# robothat.net
KiCad netlist of a schematic drawn in EAGLE
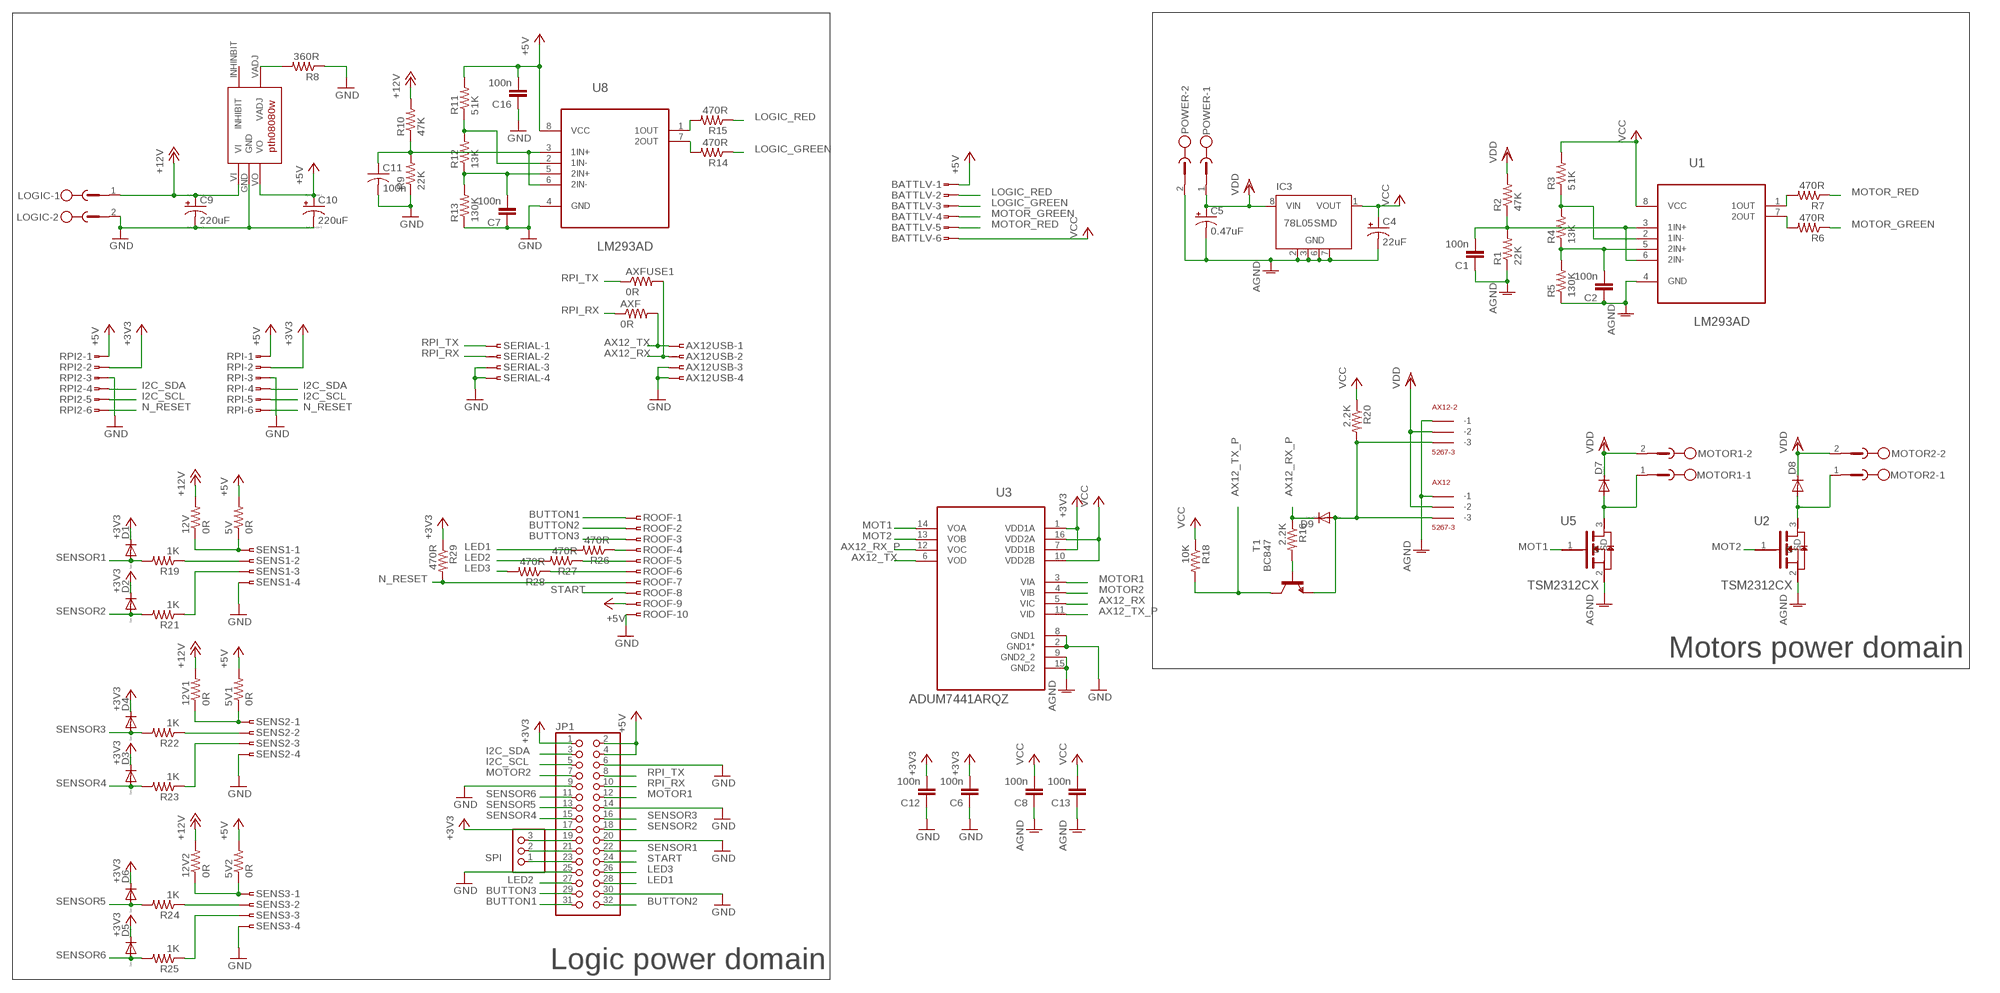
[diagram p0: schematic, sheet 1]

(export (version "E")
  (design (tool "Eeschema 10.0.6"))
  (components
    (comp (ref "5V")
      (value "0R")
      (footprint "eagle-import:R0805")
      (libsource (lib "eagle-import") (part "R-US_R0805"))
    )
    (comp (ref "5V1")
      (value "0R")
      (footprint "eagle-import:R0805")
      (libsource (lib "eagle-import") (part "R-US_R0805"))
    )
    (comp (ref "5V2")
      (value "0R")
      (footprint "eagle-import:R0805")
      (libsource (lib "eagle-import") (part "R-US_R0805"))
    )
    (comp (ref "12V")
      (value "0R")
      (footprint "eagle-import:R0805")
      (libsource (lib "eagle-import") (part "R-US_R0805"))
    )
    (comp (ref "12V1")
      (value "0R")
      (footprint "eagle-import:R0805")
      (libsource (lib "eagle-import") (part "R-US_R0805"))
    )
    (comp (ref "12V2")
      (value "0R")
      (footprint "eagle-import:R0805")
      (libsource (lib "eagle-import") (part "R-US_R0805"))
    )
    (comp (ref "AX12")
      (value "5267-3")
      (footprint "eagle-import:5267-3")
      (libsource (lib "eagle-import") (part "5267-3"))
    )
    (comp (ref "AX12-2")
      (value "5267-3")
      (footprint "eagle-import:5267-3")
      (libsource (lib "eagle-import") (part "5267-3"))
    )
    (comp (ref "AX12USB")
      (value "SMDTOP-4")
      (footprint "eagle-import:SMDTOP4")
      (libsource (lib "eagle-import") (part "SMDTOP-4"))
    )
    (comp (ref "AXF")
      (value "0R")
      (footprint "eagle-import:R0805")
      (libsource (lib "eagle-import") (part "R-US_R0805"))
    )
    (comp (ref "AXFUSE1")
      (value "0R")
      (footprint "eagle-import:R0805")
      (libsource (lib "eagle-import") (part "R-US_R0805"))
    )
    (comp (ref "BATTLV")
      (value "SMDTOP-6")
      (footprint "eagle-import:SMDTOP6")
      (libsource (lib "eagle-import") (part "SMDTOP-6"))
    )
    (comp (ref "C1")
      (value "100n")
      (footprint "eagle-import:C0805")
      (libsource (lib "eagle-import") (part "C-EUC0805"))
    )
    (comp (ref "C2")
      (value "100n")
      (footprint "eagle-import:C0805")
      (libsource (lib "eagle-import") (part "C-EUC0805"))
    )
    (comp (ref "C4")
      (value "22uF")
      (footprint "eagle-import:E2-5")
      (libsource (lib "eagle-import") (part "CPOL-USE2-5"))
    )
    (comp (ref "C5")
      (value "0.47uF")
      (footprint "eagle-import:E2-5")
      (libsource (lib "eagle-import") (part "CPOL-USE2-5"))
    )
    (comp (ref "C6")
      (value "100n")
      (footprint "eagle-import:C0805")
      (libsource (lib "eagle-import") (part "C-EUC0805"))
    )
    (comp (ref "C7")
      (value "100n")
      (footprint "eagle-import:C0805")
      (libsource (lib "eagle-import") (part "C-EUC0805"))
    )
    (comp (ref "C8")
      (value "100n")
      (footprint "eagle-import:C0805")
      (libsource (lib "eagle-import") (part "C-EUC0805"))
    )
    (comp (ref "C9")
      (value "220uF")
      (footprint "eagle-import:E3,5-8")
      (libsource (lib "eagle-import") (part "resistor_CPOL-USE3.5-8"))
    )
    (comp (ref "C10")
      (value "220uF")
      (footprint "eagle-import:E2,5-7")
      (libsource (lib "eagle-import") (part "resistor_CPOL-USE2.5-7"))
    )
    (comp (ref "C11")
      (value "100n")
      (footprint "eagle-import:C0805")
      (libsource (lib "eagle-import") (part "C-USC0805"))
    )
    (comp (ref "C12")
      (value "100n")
      (footprint "eagle-import:C0805")
      (libsource (lib "eagle-import") (part "C-EUC0805"))
    )
    (comp (ref "C13")
      (value "100n")
      (footprint "eagle-import:C0805")
      (libsource (lib "eagle-import") (part "C-EUC0805"))
    )
    (comp (ref "C16")
      (value "100n")
      (footprint "eagle-import:C0805")
      (libsource (lib "eagle-import") (part "C-EUC0805"))
    )
    (comp (ref "D1")
      (value "DIODE-SOD523")
      (footprint "eagle-import:SOD523")
      (libsource (lib "eagle-import") (part "DIODE-SOD523"))
    )
    (comp (ref "D2")
      (value "DIODE-SOD523")
      (footprint "eagle-import:SOD523")
      (libsource (lib "eagle-import") (part "DIODE-SOD523"))
    )
    (comp (ref "D3")
      (value "DIODE-SOD523")
      (footprint "eagle-import:SOD523")
      (libsource (lib "eagle-import") (part "DIODE-SOD523"))
    )
    (comp (ref "D4")
      (value "DIODE-SOD523")
      (footprint "eagle-import:SOD523")
      (libsource (lib "eagle-import") (part "DIODE-SOD523"))
    )
    (comp (ref "D5")
      (value "DIODE-SOD523")
      (footprint "eagle-import:SOD523")
      (libsource (lib "eagle-import") (part "DIODE-SOD523"))
    )
    (comp (ref "D6")
      (value "DIODE-SOD523")
      (footprint "eagle-import:SOD523")
      (libsource (lib "eagle-import") (part "DIODE-SOD523"))
    )
    (comp (ref "D7")
      (value "DIODE-SOD323-R")
      (footprint "eagle-import:SOD323-R")
      (libsource (lib "eagle-import") (part "DIODE-SOD323-R"))
    )
    (comp (ref "D8")
      (value "DIODE-SOD323-R")
      (footprint "eagle-import:SOD323-R")
      (libsource (lib "eagle-import") (part "DIODE-SOD323-R"))
    )
    (comp (ref "D9")
      (value "DIODE-SOD523")
      (footprint "eagle-import:SOD523")
      (libsource (lib "eagle-import") (part "DIODE-SOD523"))
    )
    (comp (ref "IC3")
      (value "78L05SMD")
      (footprint "eagle-import:SO08")
      (libsource (lib "eagle-import") (part "78LSMD05"))
    )
    (comp (ref "JP1")
      (value "PINHD-2X16")
      (footprint "eagle-import:2X16")
      (libsource (lib "eagle-import") (part "PINHD-2X16"))
    )
    (comp (ref "LOGIC")
      (value "MSTBV2")
      (footprint "eagle-import:MSTBV2")
      (libsource (lib "eagle-import") (part "MSTBV2"))
    )
    (comp (ref "MOTOR1")
      (value "MSTBV2")
      (footprint "eagle-import:MSTBV2")
      (libsource (lib "eagle-import") (part "MSTBV2"))
    )
    (comp (ref "MOTOR2")
      (value "MSTBV2")
      (footprint "eagle-import:MSTBV2")
      (libsource (lib "eagle-import") (part "MSTBV2"))
    )
    (comp (ref "POWER")
      (value "MSTBV2")
      (footprint "eagle-import:MSTBV2")
      (libsource (lib "eagle-import") (part "MSTBV2"))
    )
    (comp (ref "R1")
      (value "22K")
      (footprint "eagle-import:R0805")
      (libsource (lib "eagle-import") (part "R-US_R0805"))
    )
    (comp (ref "R2")
      (value "47K")
      (footprint "eagle-import:R0805")
      (libsource (lib "eagle-import") (part "R-US_R0805"))
    )
    (comp (ref "R3")
      (value "51K")
      (footprint "eagle-import:R0805")
      (libsource (lib "eagle-import") (part "R-US_R0805"))
    )
    (comp (ref "R4")
      (value "13K")
      (footprint "eagle-import:R0805")
      (libsource (lib "eagle-import") (part "R-US_R0805"))
    )
    (comp (ref "R5")
      (value "130K")
      (footprint "eagle-import:R0805")
      (libsource (lib "eagle-import") (part "R-US_R0805"))
    )
    (comp (ref "R6")
      (value "470R")
      (footprint "eagle-import:R0805")
      (libsource (lib "eagle-import") (part "R-US_R0805"))
    )
    (comp (ref "R7")
      (value "470R")
      (footprint "eagle-import:R0805")
      (libsource (lib "eagle-import") (part "R-US_R0805"))
    )
    (comp (ref "R8")
      (value "360R")
      (footprint "eagle-import:R0805")
      (libsource (lib "eagle-import") (part "R-US_R0805"))
    )
    (comp (ref "R9")
      (value "22K")
      (footprint "eagle-import:R0805")
      (libsource (lib "eagle-import") (part "R-US_R0805"))
    )
    (comp (ref "R10")
      (value "47K")
      (footprint "eagle-import:R0805")
      (libsource (lib "eagle-import") (part "R-US_R0805"))
    )
    (comp (ref "R11")
      (value "51K")
      (footprint "eagle-import:R0805")
      (libsource (lib "eagle-import") (part "R-US_R0805"))
    )
    (comp (ref "R12")
      (value "13K")
      (footprint "eagle-import:R0805")
      (libsource (lib "eagle-import") (part "R-US_R0805"))
    )
    (comp (ref "R13")
      (value "130K")
      (footprint "eagle-import:R0805")
      (libsource (lib "eagle-import") (part "R-US_R0805"))
    )
    (comp (ref "R14")
      (value "470R")
      (footprint "eagle-import:R0805")
      (libsource (lib "eagle-import") (part "R-US_R0805"))
    )
    (comp (ref "R15")
      (value "470R")
      (footprint "eagle-import:R0805")
      (libsource (lib "eagle-import") (part "R-US_R0805"))
    )
    (comp (ref "R16")
      (value "2.2K")
      (footprint "eagle-import:R0805")
      (libsource (lib "eagle-import") (part "R-US_R0805"))
    )
    (comp (ref "R18")
      (value "10K")
      (footprint "eagle-import:R0805")
      (libsource (lib "eagle-import") (part "R-US_R0805"))
    )
    (comp (ref "R19")
      (value "1K")
      (footprint "eagle-import:R0805")
      (libsource (lib "eagle-import") (part "R-US_R0805"))
    )
    (comp (ref "R20")
      (value "2.2K")
      (footprint "eagle-import:R0805")
      (libsource (lib "eagle-import") (part "R-US_R0805"))
    )
    (comp (ref "R21")
      (value "1K")
      (footprint "eagle-import:R0805")
      (libsource (lib "eagle-import") (part "R-US_R0805"))
    )
    (comp (ref "R22")
      (value "1K")
      (footprint "eagle-import:R0805")
      (libsource (lib "eagle-import") (part "R-US_R0805"))
    )
    (comp (ref "R23")
      (value "1K")
      (footprint "eagle-import:R0805")
      (libsource (lib "eagle-import") (part "R-US_R0805"))
    )
    (comp (ref "R24")
      (value "1K")
      (footprint "eagle-import:R0805")
      (libsource (lib "eagle-import") (part "R-US_R0805"))
    )
    (comp (ref "R25")
      (value "1K")
      (footprint "eagle-import:R0805")
      (libsource (lib "eagle-import") (part "R-US_R0805"))
    )
    (comp (ref "R26")
      (value "470R")
      (footprint "eagle-import:R0805")
      (libsource (lib "eagle-import") (part "R-US_R0805"))
    )
    (comp (ref "R27")
      (value "470R")
      (footprint "eagle-import:R0805")
      (libsource (lib "eagle-import") (part "R-US_R0805"))
    )
    (comp (ref "R28")
      (value "470R")
      (footprint "eagle-import:R0805")
      (libsource (lib "eagle-import") (part "R-US_R0805"))
    )
    (comp (ref "R29")
      (value "470R")
      (footprint "eagle-import:R0805")
      (libsource (lib "eagle-import") (part "R-US_R0805"))
    )
    (comp (ref "ROOF")
      (value "SMDTOP-10")
      (footprint "eagle-import:SMDTOP10")
      (libsource (lib "eagle-import") (part "SMDTOP-10"))
    )
    (comp (ref "RPI")
      (value "SMDTOP-6")
      (footprint "eagle-import:SMDTOP6")
      (libsource (lib "eagle-import") (part "SMDTOP-6"))
    )
    (comp (ref "RPI2")
      (value "SMDTOP-6")
      (footprint "eagle-import:SMDTOP6")
      (libsource (lib "eagle-import") (part "SMDTOP-6"))
    )
    (comp (ref "SENS1")
      (value "SMDTOP-4")
      (footprint "eagle-import:SMDTOP4")
      (libsource (lib "eagle-import") (part "SMDTOP-4"))
    )
    (comp (ref "SENS2")
      (value "SMDTOP-4")
      (footprint "eagle-import:SMDTOP4")
      (libsource (lib "eagle-import") (part "SMDTOP-4"))
    )
    (comp (ref "SENS3")
      (value "SMDTOP-4")
      (footprint "eagle-import:SMDTOP4")
      (libsource (lib "eagle-import") (part "SMDTOP-4"))
    )
    (comp (ref "SERIAL")
      (value "SMDTOP-4")
      (footprint "eagle-import:SMDTOP4")
      (libsource (lib "eagle-import") (part "SMDTOP-4"))
    )
    (comp (ref "SPI")
      (value "PINHD-1X3")
      (footprint "eagle-import:1X03")
      (libsource (lib "eagle-import") (part "PINHD-1X3"))
    )
    (comp (ref "T1")
      (value "BC847")
      (footprint "eagle-import:SOT23")
      (libsource (lib "eagle-import") (part "BC847"))
    )
    (comp (ref "U$2")
      (value "REGUL_PTH")
      (footprint "eagle-import:REGUL_PTH")
      (libsource (lib "eagle-import") (part "REGUL_PTH"))
    )
    (comp (ref "U1")
      (value "LM293AD")
      (footprint "eagle-import:SOIC127P600X175-8N")
      (libsource (lib "eagle-import") (part "LM293AD"))
    )
    (comp (ref "U2")
      (value "TSM2312CX")
      (footprint "eagle-import:SOT95P280X130-3N")
      (fields (field (name "MPN") "TSM2306CX"))
      (libsource (lib "eagle-import") (part "TSM2306CX"))
    )
    (comp (ref "U3")
      (value "ADUM7441ARQZ")
      (footprint "eagle-import:SOP64P600X175-16N")
      (libsource (lib "eagle-import") (part "ADUM7441ARQZ"))
    )
    (comp (ref "U5")
      (value "TSM2312CX")
      (footprint "eagle-import:SOT95P280X130-3N")
      (fields (field (name "MPN") "TSM2306CX"))
      (libsource (lib "eagle-import") (part "TSM2306CX"))
    )
    (comp (ref "U8")
      (value "LM293AD")
      (footprint "eagle-import:SOIC127P600X175-8N")
      (libsource (lib "eagle-import") (part "LM293AD"))
    )
  )
  (nets
    (net (code "1") (name "+3V3") (class "Default")
      (node (ref "C12") (pin "2") (pinfunction "2_2") (pintype "passive"))
      (node (ref "C6") (pin "2") (pinfunction "2_2") (pintype "passive"))
      (node (ref "D1") (pin "C") (pinfunction "C_C") (pintype "passive"))
      (node (ref "D2") (pin "C") (pinfunction "C_C") (pintype "passive"))
      (node (ref "D3") (pin "C") (pinfunction "C_C") (pintype "passive"))
      (node (ref "D4") (pin "C") (pinfunction "C_C") (pintype "passive"))
      (node (ref "D5") (pin "C") (pinfunction "C_C") (pintype "passive"))
      (node (ref "D6") (pin "C") (pinfunction "C_C") (pintype "passive"))
      (node (ref "JP1") (pin "1") (pinfunction "1_1") (pintype "passive"))
      (node (ref "JP1") (pin "17") (pinfunction "17_17") (pintype "passive"))
      (node (ref "R29") (pin "1") (pinfunction "1_1") (pintype "passive"))
      (node (ref "RPI") (pin "2") (pinfunction "1_2") (pintype "passive"))
      (node (ref "RPI2") (pin "2") (pinfunction "1_2") (pintype "passive"))
      (node (ref "U3") (pin "1") (pinfunction "VDD1A_1") (pintype "power_in"))
      (node (ref "U3") (pin "7") (pinfunction "VDD1B_7") (pintype "power_in"))
    )
    (net (code "2") (name "+5V") (class "Default")
      (node (ref "5V") (pin "2") (pinfunction "2_2") (pintype "passive"))
      (node (ref "5V1") (pin "2") (pinfunction "2_2") (pintype "passive"))
      (node (ref "5V2") (pin "2") (pinfunction "2_2") (pintype "passive"))
      (node (ref "BATTLV") (pin "1") (pinfunction "1_1") (pintype "passive"))
      (node (ref "C10") (pin "+") (pinfunction "+_+") (pintype "passive"))
      (node (ref "C16") (pin "2") (pinfunction "2_2") (pintype "passive"))
      (node (ref "JP1") (pin "2") (pinfunction "2_2") (pintype "passive"))
      (node (ref "JP1") (pin "4") (pinfunction "4_4") (pintype "passive"))
      (node (ref "R11") (pin "2") (pinfunction "2_2") (pintype "passive"))
      (node (ref "ROOF") (pin "9") (pinfunction "1_9") (pintype "passive"))
      (node (ref "RPI") (pin "1") (pinfunction "1_1") (pintype "passive"))
      (node (ref "RPI2") (pin "1") (pinfunction "1_1") (pintype "passive"))
      (node (ref "U$2") (pin "VO") (pinfunction "VO_VO") (pintype "bidirectional"))
      (node (ref "U8") (pin "8") (pinfunction "VCC_8") (pintype "power_in"))
    )
    (net (code "3") (name "+12V") (class "Default")
      (node (ref "12V") (pin "2") (pinfunction "2_2") (pintype "passive"))
      (node (ref "12V1") (pin "2") (pinfunction "2_2") (pintype "passive"))
      (node (ref "12V2") (pin "2") (pinfunction "2_2") (pintype "passive"))
      (node (ref "C9") (pin "+") (pinfunction "+_+") (pintype "passive"))
      (node (ref "LOGIC") (pin "1") (pinfunction "SK_1") (pintype "passive"))
      (node (ref "R10") (pin "2") (pinfunction "2_2") (pintype "passive"))
      (node (ref "U$2") (pin "VI") (pinfunction "VI_VI") (pintype "bidirectional"))
    )
    (net (code "4") (name "/AX12_RX") (class "Default")
      (node (ref "AX12USB") (pin "2") (pinfunction "1_2") (pintype "passive"))
      (node (ref "AXFUSE1") (pin "2") (pinfunction "2_2") (pintype "passive"))
      (node (ref "U3") (pin "5") (pinfunction "VIC_5") (pintype "input"))
    )
    (net (code "5") (name "/AX12_RX_P") (class "Default")
      (node (ref "D9") (pin "C") (pinfunction "C_C") (pintype "passive"))
      (node (ref "R16") (pin "1") (pinfunction "1_1") (pintype "passive"))
      (node (ref "U3") (pin "12") (pinfunction "VOC_12") (pintype "output"))
    )
    (net (code "6") (name "/AX12_TX") (class "Default")
      (node (ref "AX12USB") (pin "1") (pinfunction "1_1") (pintype "passive"))
      (node (ref "AXF") (pin "2") (pinfunction "2_2") (pintype "passive"))
      (node (ref "U3") (pin "6") (pinfunction "VOD_6") (pintype "output"))
    )
    (net (code "7") (name "/AX12_TX_P") (class "Default")
      (node (ref "R18") (pin "2") (pinfunction "2_2") (pintype "passive"))
      (node (ref "T1") (pin "3") (pinfunction "C_3") (pintype "passive"))
      (node (ref "U3") (pin "11") (pinfunction "VID_11") (pintype "input"))
    )
    (net (code "8") (name "/BUTTON1") (class "Default")
      (node (ref "JP1") (pin "31") (pinfunction "31_31") (pintype "passive"))
      (node (ref "ROOF") (pin "1") (pinfunction "1_1") (pintype "passive"))
    )
    (net (code "9") (name "/BUTTON2") (class "Default")
      (node (ref "JP1") (pin "32") (pinfunction "32_32") (pintype "passive"))
      (node (ref "ROOF") (pin "2") (pinfunction "1_2") (pintype "passive"))
    )
    (net (code "10") (name "/BUTTON3") (class "Default")
      (node (ref "JP1") (pin "29") (pinfunction "29_29") (pintype "passive"))
      (node (ref "ROOF") (pin "3") (pinfunction "1_3") (pintype "passive"))
    )
    (net (code "11") (name "/I2C_SCL") (class "Default")
      (node (ref "JP1") (pin "5") (pinfunction "5_5") (pintype "passive"))
      (node (ref "RPI") (pin "5") (pinfunction "1_5") (pintype "passive"))
      (node (ref "RPI2") (pin "5") (pinfunction "1_5") (pintype "passive"))
    )
    (net (code "12") (name "/I2C_SDA") (class "Default")
      (node (ref "JP1") (pin "3") (pinfunction "3_3") (pintype "passive"))
      (node (ref "RPI") (pin "4") (pinfunction "1_4") (pintype "passive"))
      (node (ref "RPI2") (pin "4") (pinfunction "1_4") (pintype "passive"))
    )
    (net (code "13") (name "/LED1") (class "Default")
      (node (ref "JP1") (pin "28") (pinfunction "28_28") (pintype "passive"))
      (node (ref "R26") (pin "2") (pinfunction "2_2") (pintype "passive"))
    )
    (net (code "14") (name "/LED2") (class "Default")
      (node (ref "JP1") (pin "27") (pinfunction "27_27") (pintype "passive"))
      (node (ref "R27") (pin "2") (pinfunction "2_2") (pintype "passive"))
    )
    (net (code "15") (name "/LED3") (class "Default")
      (node (ref "JP1") (pin "26") (pinfunction "26_26") (pintype "passive"))
      (node (ref "R28") (pin "2") (pinfunction "2_2") (pintype "passive"))
    )
    (net (code "16") (name "/LOGIC_GREEN") (class "Default")
      (node (ref "BATTLV") (pin "3") (pinfunction "1_3") (pintype "passive"))
      (node (ref "R14") (pin "1") (pinfunction "1_1") (pintype "passive"))
    )
    (net (code "17") (name "/LOGIC_RED") (class "Default")
      (node (ref "BATTLV") (pin "2") (pinfunction "1_2") (pintype "passive"))
      (node (ref "R15") (pin "1") (pinfunction "1_1") (pintype "passive"))
    )
    (net (code "18") (name "/MOT1") (class "Default")
      (node (ref "U3") (pin "14") (pinfunction "VOA_14") (pintype "output"))
      (node (ref "U5") (pin "1") (pinfunction "G_1") (pintype "input"))
    )
    (net (code "19") (name "/MOT2") (class "Default")
      (node (ref "U2") (pin "1") (pinfunction "G_1") (pintype "input"))
      (node (ref "U3") (pin "13") (pinfunction "VOB_13") (pintype "output"))
    )
    (net (code "20") (name "/MOTOR1") (class "Default")
      (node (ref "JP1") (pin "12") (pinfunction "12_12") (pintype "passive"))
      (node (ref "U3") (pin "3") (pinfunction "VIA_3") (pintype "input"))
    )
    (net (code "21") (name "/MOTOR2") (class "Default")
      (node (ref "JP1") (pin "7") (pinfunction "7_7") (pintype "passive"))
      (node (ref "U3") (pin "4") (pinfunction "VIB_4") (pintype "input"))
    )
    (net (code "22") (name "/MOTOR_GREEN") (class "Default")
      (node (ref "BATTLV") (pin "4") (pinfunction "1_4") (pintype "passive"))
      (node (ref "R6") (pin "1") (pinfunction "1_1") (pintype "passive"))
    )
    (net (code "23") (name "/MOTOR_RED") (class "Default")
      (node (ref "BATTLV") (pin "5") (pinfunction "1_5") (pintype "passive"))
      (node (ref "R7") (pin "1") (pinfunction "1_1") (pintype "passive"))
    )
    (net (code "24") (name "/N_RESET") (class "Default")
      (node (ref "R29") (pin "2") (pinfunction "2_2") (pintype "passive"))
      (node (ref "ROOF") (pin "7") (pinfunction "1_7") (pintype "passive"))
      (node (ref "RPI") (pin "6") (pinfunction "1_6") (pintype "passive"))
      (node (ref "RPI2") (pin "6") (pinfunction "1_6") (pintype "passive"))
    )
    (net (code "25") (name "/RPI_RX") (class "Default")
      (node (ref "AXF") (pin "1") (pinfunction "1_1") (pintype "passive"))
      (node (ref "JP1") (pin "10") (pinfunction "10_10") (pintype "passive"))
      (node (ref "SERIAL") (pin "2") (pinfunction "1_2") (pintype "passive"))
    )
    (net (code "26") (name "/RPI_TX") (class "Default")
      (node (ref "AXFUSE1") (pin "1") (pinfunction "1_1") (pintype "passive"))
      (node (ref "JP1") (pin "8") (pinfunction "8_8") (pintype "passive"))
      (node (ref "SERIAL") (pin "1") (pinfunction "1_1") (pintype "passive"))
    )
    (net (code "27") (name "/SENSOR1") (class "Default")
      (node (ref "D1") (pin "A") (pinfunction "A_A") (pintype "passive"))
      (node (ref "JP1") (pin "22") (pinfunction "22_22") (pintype "passive"))
      (node (ref "R19") (pin "2") (pinfunction "2_2") (pintype "passive"))
    )
    (net (code "28") (name "/SENSOR2") (class "Default")
      (node (ref "D2") (pin "A") (pinfunction "A_A") (pintype "passive"))
      (node (ref "JP1") (pin "18") (pinfunction "18_18") (pintype "passive"))
      (node (ref "R21") (pin "2") (pinfunction "2_2") (pintype "passive"))
    )
    (net (code "29") (name "/SENSOR3") (class "Default")
      (node (ref "D4") (pin "A") (pinfunction "A_A") (pintype "passive"))
      (node (ref "JP1") (pin "16") (pinfunction "16_16") (pintype "passive"))
      (node (ref "R22") (pin "2") (pinfunction "2_2") (pintype "passive"))
    )
    (net (code "30") (name "/SENSOR4") (class "Default")
      (node (ref "D3") (pin "A") (pinfunction "A_A") (pintype "passive"))
      (node (ref "JP1") (pin "15") (pinfunction "15_15") (pintype "passive"))
      (node (ref "R23") (pin "2") (pinfunction "2_2") (pintype "passive"))
    )
    (net (code "31") (name "/SENSOR5") (class "Default")
      (node (ref "D6") (pin "A") (pinfunction "A_A") (pintype "passive"))
      (node (ref "JP1") (pin "13") (pinfunction "13_13") (pintype "passive"))
      (node (ref "R24") (pin "2") (pinfunction "2_2") (pintype "passive"))
    )
    (net (code "32") (name "/SENSOR6") (class "Default")
      (node (ref "D5") (pin "A") (pinfunction "A_A") (pintype "passive"))
      (node (ref "JP1") (pin "11") (pinfunction "11_11") (pintype "passive"))
      (node (ref "R25") (pin "2") (pinfunction "2_2") (pintype "passive"))
    )
    (net (code "33") (name "/START") (class "Default")
      (node (ref "JP1") (pin "24") (pinfunction "24_24") (pintype "passive"))
      (node (ref "ROOF") (pin "8") (pinfunction "1_8") (pintype "passive"))
    )
    (net (code "34") (name "AGND") (class "Default")
      (node (ref "AX12") (pin "P$1") (pinfunction "-1_P$1") (pintype "bidirectional"))
      (node (ref "AX12-2") (pin "P$1") (pinfunction "-1_P$1") (pintype "bidirectional"))
      (node (ref "C1") (pin "1") (pinfunction "1_1") (pintype "passive"))
      (node (ref "C13") (pin "1") (pinfunction "1_1") (pintype "passive"))
      (node (ref "C2") (pin "1") (pinfunction "1_1") (pintype "passive"))
      (node (ref "C4") (pin "-") (pinfunction "-_-") (pintype "passive"))
      (node (ref "C5") (pin "-") (pinfunction "-_-") (pintype "passive"))
      (node (ref "C8") (pin "1") (pinfunction "1_1") (pintype "passive"))
      (node (ref "IC3") (pin "2") (pinfunction "GND_2") (pintype "power_in"))
      (node (ref "IC3") (pin "3") (pinfunction "GND_3") (pintype "power_in"))
      (node (ref "IC3") (pin "6") (pinfunction "GND_6") (pintype "power_in"))
      (node (ref "IC3") (pin "7") (pinfunction "GND_7") (pintype "power_in"))
      (node (ref "POWER") (pin "2") (pinfunction "SK_2") (pintype "passive"))
      (node (ref "R1") (pin "1") (pinfunction "1_1") (pintype "passive"))
      (node (ref "R5") (pin "1") (pinfunction "1_1") (pintype "passive"))
      (node (ref "U1") (pin "4") (pinfunction "GND_4") (pintype "passive"))
      (node (ref "U2") (pin "2") (pinfunction "S_2") (pintype "passive"))
      (node (ref "U3") (pin "15") (pinfunction "GND2_15") (pintype "passive"))
      (node (ref "U3") (pin "9") (pinfunction "GND2_2_9") (pintype "passive"))
      (node (ref "U5") (pin "2") (pinfunction "S_2") (pintype "passive"))
    )
    (net (code "35") (name "GND") (class "Default")
      (node (ref "AX12USB") (pin "3") (pinfunction "1_3") (pintype "passive"))
      (node (ref "AX12USB") (pin "4") (pinfunction "1_4") (pintype "passive"))
      (node (ref "C10") (pin "-") (pinfunction "-_-") (pintype "passive"))
      (node (ref "C11") (pin "2") (pinfunction "2_2") (pintype "passive"))
      (node (ref "C12") (pin "1") (pinfunction "1_1") (pintype "passive"))
      (node (ref "C16") (pin "1") (pinfunction "1_1") (pintype "passive"))
      (node (ref "C6") (pin "1") (pinfunction "1_1") (pintype "passive"))
      (node (ref "C7") (pin "1") (pinfunction "1_1") (pintype "passive"))
      (node (ref "C9") (pin "-") (pinfunction "-_-") (pintype "passive"))
      (node (ref "JP1") (pin "14") (pinfunction "14_14") (pintype "passive"))
      (node (ref "JP1") (pin "20") (pinfunction "20_20") (pintype "passive"))
      (node (ref "JP1") (pin "25") (pinfunction "25_25") (pintype "passive"))
      (node (ref "JP1") (pin "30") (pinfunction "30_30") (pintype "passive"))
      (node (ref "JP1") (pin "6") (pinfunction "6_6") (pintype "passive"))
      (node (ref "JP1") (pin "9") (pinfunction "9_9") (pintype "passive"))
      (node (ref "LOGIC") (pin "2") (pinfunction "SK_2") (pintype "passive"))
      (node (ref "R13") (pin "1") (pinfunction "1_1") (pintype "passive"))
      (node (ref "R8") (pin "1") (pinfunction "1_1") (pintype "passive"))
      (node (ref "R9") (pin "1") (pinfunction "1_1") (pintype "passive"))
      (node (ref "ROOF") (pin "10") (pinfunction "1_10") (pintype "passive"))
      (node (ref "RPI") (pin "3") (pinfunction "1_3") (pintype "passive"))
      (node (ref "RPI2") (pin "3") (pinfunction "1_3") (pintype "passive"))
      (node (ref "SENS1") (pin "4") (pinfunction "1_4") (pintype "passive"))
      (node (ref "SENS2") (pin "4") (pinfunction "1_4") (pintype "passive"))
      (node (ref "SENS3") (pin "4") (pinfunction "1_4") (pintype "passive"))
      (node (ref "SERIAL") (pin "3") (pinfunction "1_3") (pintype "passive"))
      (node (ref "SERIAL") (pin "4") (pinfunction "1_4") (pintype "passive"))
      (node (ref "U$2") (pin "GND") (pinfunction "GND_GND") (pintype "bidirectional"))
      (node (ref "U3") (pin "2") (pinfunction "GND1*_2") (pintype "passive"))
      (node (ref "U3") (pin "8") (pinfunction "GND1_8") (pintype "passive"))
      (node (ref "U8") (pin "4") (pinfunction "GND_4") (pintype "passive"))
    )
    (net (code "36") (name "Net-(12V-Pad1)") (class "Default")
      (node (ref "12V") (pin "1") (pinfunction "1_1") (pintype "passive"))
      (node (ref "5V") (pin "1") (pinfunction "1_1") (pintype "passive"))
      (node (ref "SENS1") (pin "1") (pinfunction "1_1") (pintype "passive"))
    )
    (net (code "37") (name "Net-(12V1-Pad1)") (class "Default")
      (node (ref "12V1") (pin "1") (pinfunction "1_1") (pintype "passive"))
      (node (ref "5V1") (pin "1") (pinfunction "1_1") (pintype "passive"))
      (node (ref "SENS2") (pin "1") (pinfunction "1_1") (pintype "passive"))
    )
    (net (code "38") (name "Net-(12V2-Pad1)") (class "Default")
      (node (ref "12V2") (pin "1") (pinfunction "1_1") (pintype "passive"))
      (node (ref "5V2") (pin "1") (pinfunction "1_1") (pintype "passive"))
      (node (ref "SENS3") (pin "1") (pinfunction "1_1") (pintype "passive"))
    )
    (net (code "39") (name "Net-(AX12--3)") (class "Default")
      (node (ref "AX12") (pin "P$3") (pinfunction "-3_P$3") (pintype "bidirectional"))
      (node (ref "AX12-2") (pin "P$3") (pinfunction "-3_P$3") (pintype "bidirectional"))
      (node (ref "D9") (pin "A") (pinfunction "A_A") (pintype "passive"))
      (node (ref "R20") (pin "2") (pinfunction "2_2") (pintype "passive"))
      (node (ref "T1") (pin "2") (pinfunction "E_2") (pintype "passive"))
    )
    (net (code "40") (name "Net-(JP1-Pad19)") (class "Default")
      (node (ref "JP1") (pin "19") (pinfunction "19_19") (pintype "passive"))
      (node (ref "SPI") (pin "3") (pinfunction "3_3") (pintype "passive"))
    )
    (net (code "41") (name "Net-(JP1-Pad21)") (class "Default")
      (node (ref "JP1") (pin "21") (pinfunction "21_21") (pintype "passive"))
      (node (ref "SPI") (pin "2") (pinfunction "2_2") (pintype "passive"))
    )
    (net (code "42") (name "Net-(JP1-Pad23)") (class "Default")
      (node (ref "JP1") (pin "23") (pinfunction "23_23") (pintype "passive"))
      (node (ref "SPI") (pin "1") (pinfunction "1_1") (pintype "passive"))
    )
    (net (code "43") (name "Net-(MOTOR1A-SK)") (class "Default")
      (node (ref "D7") (pin "A") (pinfunction "A_A") (pintype "passive"))
      (node (ref "MOTOR1") (pin "1") (pinfunction "SK_1") (pintype "passive"))
      (node (ref "U5") (pin "3") (pinfunction "D_3") (pintype "output"))
    )
    (net (code "44") (name "Net-(MOTOR2A-SK)") (class "Default")
      (node (ref "D8") (pin "A") (pinfunction "A_A") (pintype "passive"))
      (node (ref "MOTOR2") (pin "1") (pinfunction "SK_1") (pintype "passive"))
      (node (ref "U2") (pin "3") (pinfunction "D_3") (pintype "output"))
    )
    (net (code "45") (name "Net-(R8-Pad2)") (class "Default")
      (node (ref "R8") (pin "2") (pinfunction "2_2") (pintype "passive"))
      (node (ref "U$2") (pin "VADJ") (pinfunction "VADJ_VADJ") (pintype "bidirectional"))
    )
    (net (code "46") (name "Net-(ROOFE-1)") (class "Default")
      (node (ref "R26") (pin "1") (pinfunction "1_1") (pintype "passive"))
      (node (ref "ROOF") (pin "4") (pinfunction "1_4") (pintype "passive"))
    )
    (net (code "47") (name "Net-(ROOFF-1)") (class "Default")
      (node (ref "R27") (pin "1") (pinfunction "1_1") (pintype "passive"))
      (node (ref "ROOF") (pin "5") (pinfunction "1_5") (pintype "passive"))
    )
    (net (code "48") (name "Net-(ROOFG-1)") (class "Default")
      (node (ref "R28") (pin "1") (pinfunction "1_1") (pintype "passive"))
      (node (ref "ROOF") (pin "6") (pinfunction "1_6") (pintype "passive"))
    )
    (net (code "49") (name "Net-(SENS1B-1)") (class "Default")
      (node (ref "R19") (pin "1") (pinfunction "1_1") (pintype "passive"))
      (node (ref "SENS1") (pin "2") (pinfunction "1_2") (pintype "passive"))
    )
    (net (code "50") (name "Net-(SENS1C-1)") (class "Default")
      (node (ref "R21") (pin "1") (pinfunction "1_1") (pintype "passive"))
      (node (ref "SENS1") (pin "3") (pinfunction "1_3") (pintype "passive"))
    )
    (net (code "51") (name "Net-(SENS2B-1)") (class "Default")
      (node (ref "R22") (pin "1") (pinfunction "1_1") (pintype "passive"))
      (node (ref "SENS2") (pin "2") (pinfunction "1_2") (pintype "passive"))
    )
    (net (code "52") (name "Net-(SENS2C-1)") (class "Default")
      (node (ref "R23") (pin "1") (pinfunction "1_1") (pintype "passive"))
      (node (ref "SENS2") (pin "3") (pinfunction "1_3") (pintype "passive"))
    )
    (net (code "53") (name "Net-(SENS3B-1)") (class "Default")
      (node (ref "R24") (pin "1") (pinfunction "1_1") (pintype "passive"))
      (node (ref "SENS3") (pin "2") (pinfunction "1_2") (pintype "passive"))
    )
    (net (code "54") (name "Net-(SENS3C-1)") (class "Default")
      (node (ref "R25") (pin "1") (pinfunction "1_1") (pintype "passive"))
      (node (ref "SENS3") (pin "3") (pinfunction "1_3") (pintype "passive"))
    )
    (net (code "55") (name "Net-(T1-B)") (class "Default")
      (node (ref "R16") (pin "2") (pinfunction "2_2") (pintype "passive"))
      (node (ref "T1") (pin "1") (pinfunction "B_1") (pintype "passive"))
    )
    (net (code "56") (name "Net-(U1-1IN+)") (class "Default")
      (node (ref "C1") (pin "2") (pinfunction "2_2") (pintype "passive"))
      (node (ref "R1") (pin "2") (pinfunction "2_2") (pintype "passive"))
      (node (ref "R2") (pin "1") (pinfunction "1_1") (pintype "passive"))
      (node (ref "U1") (pin "3") (pinfunction "1IN+_3") (pintype "input"))
      (node (ref "U1") (pin "6") (pinfunction "2IN-_6") (pintype "input"))
    )
    (net (code "57") (name "Net-(U1-1IN-)") (class "Default")
      (node (ref "R3") (pin "1") (pinfunction "1_1") (pintype "passive"))
      (node (ref "R4") (pin "2") (pinfunction "2_2") (pintype "passive"))
      (node (ref "U1") (pin "2") (pinfunction "1IN-_2") (pintype "input"))
    )
    (net (code "58") (name "Net-(U1-1OUT)") (class "Default")
      (node (ref "R7") (pin "2") (pinfunction "2_2") (pintype "passive"))
      (node (ref "U1") (pin "1") (pinfunction "1OUT_1") (pintype "output"))
    )
    (net (code "59") (name "Net-(U1-2IN+)") (class "Default")
      (node (ref "C2") (pin "2") (pinfunction "2_2") (pintype "passive"))
      (node (ref "R4") (pin "1") (pinfunction "1_1") (pintype "passive"))
      (node (ref "R5") (pin "2") (pinfunction "2_2") (pintype "passive"))
      (node (ref "U1") (pin "5") (pinfunction "2IN+_5") (pintype "input"))
    )
    (net (code "60") (name "Net-(U1-2OUT)") (class "Default")
      (node (ref "R6") (pin "2") (pinfunction "2_2") (pintype "passive"))
      (node (ref "U1") (pin "7") (pinfunction "2OUT_7") (pintype "output"))
    )
    (net (code "61") (name "Net-(U8-1IN+)") (class "Default")
      (node (ref "C11") (pin "1") (pinfunction "1_1") (pintype "passive"))
      (node (ref "R10") (pin "1") (pinfunction "1_1") (pintype "passive"))
      (node (ref "R9") (pin "2") (pinfunction "2_2") (pintype "passive"))
      (node (ref "U8") (pin "3") (pinfunction "1IN+_3") (pintype "input"))
      (node (ref "U8") (pin "6") (pinfunction "2IN-_6") (pintype "input"))
    )
    (net (code "62") (name "Net-(U8-1IN-)") (class "Default")
      (node (ref "R11") (pin "1") (pinfunction "1_1") (pintype "passive"))
      (node (ref "R12") (pin "2") (pinfunction "2_2") (pintype "passive"))
      (node (ref "U8") (pin "2") (pinfunction "1IN-_2") (pintype "input"))
    )
    (net (code "63") (name "Net-(U8-1OUT)") (class "Default")
      (node (ref "R15") (pin "2") (pinfunction "2_2") (pintype "passive"))
      (node (ref "U8") (pin "1") (pinfunction "1OUT_1") (pintype "output"))
    )
    (net (code "64") (name "Net-(U8-2IN+)") (class "Default")
      (node (ref "C7") (pin "2") (pinfunction "2_2") (pintype "passive"))
      (node (ref "R12") (pin "1") (pinfunction "1_1") (pintype "passive"))
      (node (ref "R13") (pin "2") (pinfunction "2_2") (pintype "passive"))
      (node (ref "U8") (pin "5") (pinfunction "2IN+_5") (pintype "input"))
    )
    (net (code "65") (name "Net-(U8-2OUT)") (class "Default")
      (node (ref "R14") (pin "2") (pinfunction "2_2") (pintype "passive"))
      (node (ref "U8") (pin "7") (pinfunction "2OUT_7") (pintype "output"))
    )
    (net (code "66") (name "VCC") (class "Default")
      (node (ref "BATTLV") (pin "6") (pinfunction "1_6") (pintype "passive"))
      (node (ref "C13") (pin "2") (pinfunction "2_2") (pintype "passive"))
      (node (ref "C4") (pin "+") (pinfunction "+_+") (pintype "passive"))
      (node (ref "C8") (pin "2") (pinfunction "2_2") (pintype "passive"))
      (node (ref "IC3") (pin "1") (pinfunction "VOUT_1") (pintype "output"))
      (node (ref "R18") (pin "1") (pinfunction "1_1") (pintype "passive"))
      (node (ref "R20") (pin "1") (pinfunction "1_1") (pintype "passive"))
      (node (ref "R3") (pin "2") (pinfunction "2_2") (pintype "passive"))
      (node (ref "U1") (pin "8") (pinfunction "VCC_8") (pintype "power_in"))
      (node (ref "U3") (pin "10") (pinfunction "VDD2B_10") (pintype "power_in"))
      (node (ref "U3") (pin "16") (pinfunction "VDD2A_16") (pintype "power_in"))
    )
    (net (code "67") (name "VDD") (class "Default")
      (node (ref "AX12") (pin "P$2") (pinfunction "-2_P$2") (pintype "bidirectional"))
      (node (ref "AX12-2") (pin "P$2") (pinfunction "-2_P$2") (pintype "bidirectional"))
      (node (ref "C5") (pin "+") (pinfunction "+_+") (pintype "passive"))
      (node (ref "D7") (pin "C") (pinfunction "C_C") (pintype "passive"))
      (node (ref "D8") (pin "C") (pinfunction "C_C") (pintype "passive"))
      (node (ref "IC3") (pin "8") (pinfunction "VIN_8") (pintype "passive"))
      (node (ref "MOTOR1") (pin "2") (pinfunction "SK_2") (pintype "passive"))
      (node (ref "MOTOR2") (pin "2") (pinfunction "SK_2") (pintype "passive"))
      (node (ref "POWER") (pin "1") (pinfunction "SK_1") (pintype "passive"))
      (node (ref "R2") (pin "2") (pinfunction "2_2") (pintype "passive"))
    )
    (net (code "68") (name "unconnected-(U$2-INHIBIT-PadINHINBIT)") (class "Default")
      (node (ref "U$2") (pin "INHINBIT") (pinfunction "INHIBIT_INHINBIT") (pintype "bidirectional"))
    )
  )
)
